# Line_sensors.net
KiCad netlist of a schematic drawn in EAGLE
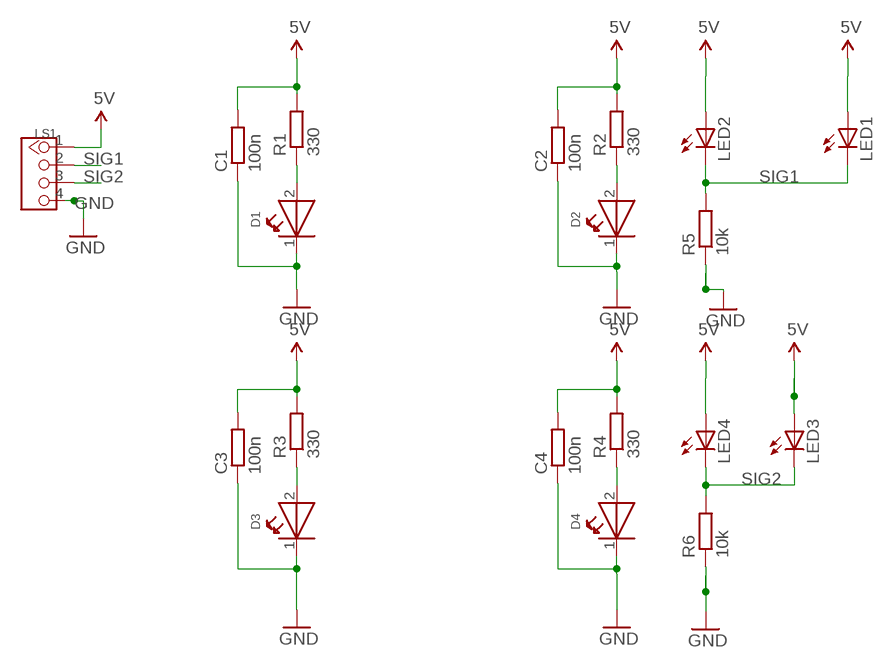
[diagram p0: schematic, sheet 1]

(export (version "E")
  (design (tool "Eeschema 10.0.6"))
  (components
    (comp (ref "C1")
      (value "100n")
      (footprint "eagle-import:M0805")
      (libsource (lib "eagle-import") (part "R-EU_M0805"))
    )
    (comp (ref "C2")
      (value "100n")
      (footprint "eagle-import:M0805")
      (libsource (lib "eagle-import") (part "R-EU_M0805"))
    )
    (comp (ref "C3")
      (value "100n")
      (footprint "eagle-import:M0805")
      (libsource (lib "eagle-import") (part "R-EU_M0805"))
    )
    (comp (ref "C4")
      (value "100n")
      (footprint "eagle-import:M0805")
      (libsource (lib "eagle-import") (part "R-EU_M0805"))
    )
    (comp (ref "D1")
      (value "WL-SMTW-150141AS73100-A")
      (footprint "eagle-import:3528-2PIN")
      (fields
        (field (name "MANUFACTURER") "Würth Elektronik eiSos GmbH")
        (field (name "CREATED-BY") "Christin Otto")
      )
      (libsource (lib "eagle-import") (part "WL-SMTW-150141AS73100-A"))
    )
    (comp (ref "D2")
      (value "WL-SMTW-150141AS73100-A")
      (footprint "eagle-import:3528-2PIN")
      (fields
        (field (name "MANUFACTURER") "Würth Elektronik eiSos GmbH")
        (field (name "CREATED-BY") "Christin Otto")
      )
      (libsource (lib "eagle-import") (part "WL-SMTW-150141AS73100-A"))
    )
    (comp (ref "D3")
      (value "WL-SMTW-150141AS73100-A")
      (footprint "eagle-import:3528-2PIN")
      (fields
        (field (name "MANUFACTURER") "Würth Elektronik eiSos GmbH")
        (field (name "CREATED-BY") "Christin Otto")
      )
      (libsource (lib "eagle-import") (part "WL-SMTW-150141AS73100-A"))
    )
    (comp (ref "D4")
      (value "WL-SMTW-150141AS73100-A")
      (footprint "eagle-import:3528-2PIN")
      (fields
        (field (name "MANUFACTURER") "Würth Elektronik eiSos GmbH")
        (field (name "CREATED-BY") "Christin Otto")
      )
      (libsource (lib "eagle-import") (part "WL-SMTW-150141AS73100-A"))
    )
    (comp (ref "LED1")
      (value "LED3MM")
      (footprint "eagle-import:LED3MM")
      (libsource (lib "eagle-import") (part "LED3MM"))
    )
    (comp (ref "LED2")
      (value "LED3MM")
      (footprint "eagle-import:LED3MM")
      (libsource (lib "eagle-import") (part "LED3MM"))
    )
    (comp (ref "LED3")
      (value "LED3MM")
      (footprint "eagle-import:LED3MM")
      (libsource (lib "eagle-import") (part "LED3MM"))
    )
    (comp (ref "LED4")
      (value "LED3MM")
      (footprint "eagle-import:LED3MM")
      (libsource (lib "eagle-import") (part "LED3MM"))
    )
    (comp (ref "LS1")
      (value "TWIG-4P-2.0-2.0")
      (footprint "eagle-import:4P-2.0")
      (libsource (lib "eagle-import") (part "TWIG-4P-2.0-2.0"))
    )
    (comp (ref "R1")
      (value "330")
      (footprint "eagle-import:M0805")
      (libsource (lib "eagle-import") (part "R-EU_M0805"))
    )
    (comp (ref "R2")
      (value "330")
      (footprint "eagle-import:M0805")
      (libsource (lib "eagle-import") (part "R-EU_M0805"))
    )
    (comp (ref "R3")
      (value "330")
      (footprint "eagle-import:M0805")
      (libsource (lib "eagle-import") (part "R-EU_M0805"))
    )
    (comp (ref "R4")
      (value "330")
      (footprint "eagle-import:M0805")
      (libsource (lib "eagle-import") (part "R-EU_M0805"))
    )
    (comp (ref "R5")
      (value "10k")
      (footprint "eagle-import:M0805")
      (libsource (lib "eagle-import") (part "R-EU_M0805"))
    )
    (comp (ref "R6")
      (value "10k")
      (footprint "eagle-import:M0805")
      (libsource (lib "eagle-import") (part "R-EU_M0805"))
    )
  )
  (nets
    (net (code "1") (name "/SIG1") (class "Default")
      (node (ref "LED1") (pin "K") (pinfunction "C_K") (pintype "passive"))
      (node (ref "LED2") (pin "K") (pinfunction "C_K") (pintype "passive"))
      (node (ref "LS1") (pin "2") (pinfunction "2_2") (pintype "bidirectional"))
      (node (ref "R5") (pin "2") (pinfunction "2_2") (pintype "passive"))
    )
    (net (code "2") (name "/SIG2") (class "Default")
      (node (ref "LED3") (pin "K") (pinfunction "C_K") (pintype "passive"))
      (node (ref "LED4") (pin "K") (pinfunction "C_K") (pintype "passive"))
      (node (ref "LS1") (pin "3") (pinfunction "3_3") (pintype "bidirectional"))
      (node (ref "R6") (pin "2") (pinfunction "2_2") (pintype "passive"))
    )
    (net (code "3") (name "5V") (class "Default")
      (node (ref "C1") (pin "2") (pinfunction "2_2") (pintype "passive"))
      (node (ref "C2") (pin "2") (pinfunction "2_2") (pintype "passive"))
      (node (ref "C3") (pin "2") (pinfunction "2_2") (pintype "passive"))
      (node (ref "C4") (pin "2") (pinfunction "2_2") (pintype "passive"))
      (node (ref "LED1") (pin "A") (pinfunction "A_A") (pintype "passive"))
      (node (ref "LED2") (pin "A") (pinfunction "A_A") (pintype "passive"))
      (node (ref "LED3") (pin "A") (pinfunction "A_A") (pintype "passive"))
      (node (ref "LED4") (pin "A") (pinfunction "A_A") (pintype "passive"))
      (node (ref "LS1") (pin "1") (pinfunction "1_1") (pintype "bidirectional"))
      (node (ref "R1") (pin "2") (pinfunction "2_2") (pintype "passive"))
      (node (ref "R2") (pin "2") (pinfunction "2_2") (pintype "passive"))
      (node (ref "R3") (pin "2") (pinfunction "2_2") (pintype "passive"))
      (node (ref "R4") (pin "2") (pinfunction "2_2") (pintype "passive"))
    )
    (net (code "4") (name "GND") (class "Default")
      (node (ref "C1") (pin "1") (pinfunction "1_1") (pintype "passive"))
      (node (ref "C2") (pin "1") (pinfunction "1_1") (pintype "passive"))
      (node (ref "C3") (pin "1") (pinfunction "1_1") (pintype "passive"))
      (node (ref "C4") (pin "1") (pinfunction "1_1") (pintype "passive"))
      (node (ref "D1") (pin "1") (pinfunction "K_1") (pintype "bidirectional"))
      (node (ref "D2") (pin "1") (pinfunction "K_1") (pintype "bidirectional"))
      (node (ref "D3") (pin "1") (pinfunction "K_1") (pintype "bidirectional"))
      (node (ref "D4") (pin "1") (pinfunction "K_1") (pintype "bidirectional"))
      (node (ref "LS1") (pin "4") (pinfunction "4_4") (pintype "bidirectional"))
      (node (ref "R5") (pin "1") (pinfunction "1_1") (pintype "passive"))
      (node (ref "R6") (pin "1") (pinfunction "1_1") (pintype "passive"))
    )
    (net (code "5") (name "Net-(D1-A)") (class "Default")
      (node (ref "D1") (pin "2") (pinfunction "A_2") (pintype "bidirectional"))
      (node (ref "R1") (pin "1") (pinfunction "1_1") (pintype "passive"))
    )
    (net (code "6") (name "Net-(D2-A)") (class "Default")
      (node (ref "D2") (pin "2") (pinfunction "A_2") (pintype "bidirectional"))
      (node (ref "R2") (pin "1") (pinfunction "1_1") (pintype "passive"))
    )
    (net (code "7") (name "Net-(D3-A)") (class "Default")
      (node (ref "D3") (pin "2") (pinfunction "A_2") (pintype "bidirectional"))
      (node (ref "R3") (pin "1") (pinfunction "1_1") (pintype "passive"))
    )
    (net (code "8") (name "Net-(D4-A)") (class "Default")
      (node (ref "D4") (pin "2") (pinfunction "A_2") (pintype "bidirectional"))
      (node (ref "R4") (pin "1") (pinfunction "1_1") (pintype "passive"))
    )
  )
)
